# RTL8201CL_Demo.net
KiCad netlist of a schematic drawn in Altium Designer
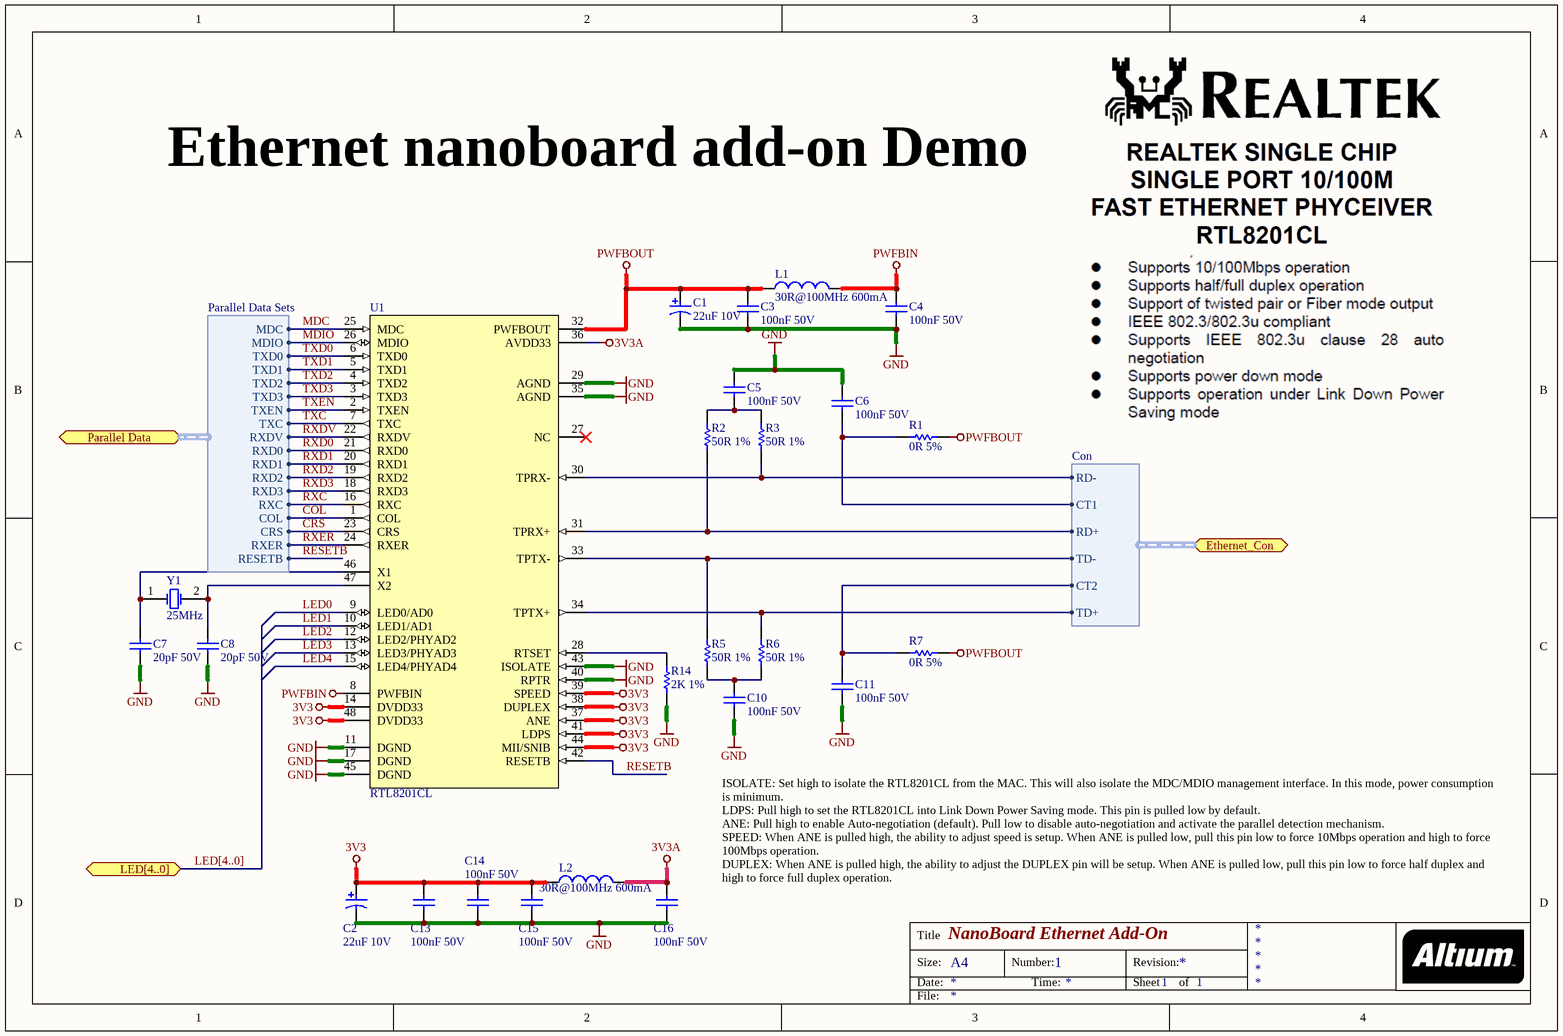
[diagram p0: RTL8201CL_Demo.SchDoc]

(export (version "E")
  (design (tool "Eeschema 10.0.6"))
  (components
    (comp (ref "C1")
      (value "22uF 10V")
      (footprint "PHY_Demo:CAPC3528")
      (description "Polar Capacitor")
      (libsource (lib "Altium Design Library") (part "CAP-P"))
    )
    (comp (ref "C2")
      (value "22uF 10V")
      (footprint "PHY_Demo:CAPC3528")
      (description "Polar Capacitor")
      (libsource (lib "Altium Design Library") (part "CAP-P"))
    )
    (comp (ref "C3")
      (value "100nF 50V")
      (footprint "PHY_Demo:CAPC2012")
      (description "Capacitor")
      (libsource (lib "Altium Design Library") (part "CAP-NP"))
    )
    (comp (ref "C4")
      (value "100nF 50V")
      (footprint "PHY_Demo:CAPC2012")
      (description "Capacitor")
      (libsource (lib "Altium Design Library") (part "CAP-NP"))
    )
    (comp (ref "C5")
      (value "100nF 50V")
      (footprint "PHY_Demo:CAPC2012")
      (description "Capacitor")
      (libsource (lib "Altium Design Library") (part "CAP-NP"))
    )
    (comp (ref "C6")
      (value "100nF 50V")
      (footprint "PHY_Demo:CAPC2012")
      (description "Capacitor")
      (libsource (lib "Altium Design Library") (part "CAP-NP"))
    )
    (comp (ref "C7")
      (value "20pF 50V")
      (footprint "PHY_Demo:CAPC2012")
      (description "Capacitor")
      (libsource (lib "Altium Design Library") (part "CAP-NP"))
    )
    (comp (ref "C8")
      (value "20pF 50V")
      (footprint "PHY_Demo:CAPC2012")
      (description "Capacitor")
      (libsource (lib "Altium Design Library") (part "CAP-NP"))
    )
    (comp (ref "C10")
      (value "100nF 50V")
      (footprint "PHY_Demo:CAPC2012")
      (description "Capacitor")
      (libsource (lib "Altium Design Library") (part "CAP-NP"))
    )
    (comp (ref "C11")
      (value "100nF 50V")
      (footprint "PHY_Demo:CAPC2012")
      (description "Capacitor")
      (libsource (lib "Altium Design Library") (part "CAP-NP"))
    )
    (comp (ref "C13")
      (value "100nF 50V")
      (footprint "PHY_Demo:CAPC2012")
      (description "Capacitor")
      (libsource (lib "Altium Design Library") (part "CAP-NP"))
    )
    (comp (ref "C14")
      (value "100nF 50V")
      (footprint "PHY_Demo:CAPC2012")
      (description "Capacitor")
      (libsource (lib "Altium Design Library") (part "CAP-NP"))
    )
    (comp (ref "C15")
      (value "100nF 50V")
      (footprint "PHY_Demo:CAPC2012")
      (description "Capacitor")
      (libsource (lib "Altium Design Library") (part "CAP-NP"))
    )
    (comp (ref "C16")
      (value "100nF 50V")
      (footprint "PHY_Demo:CAPC2012")
      (description "Capacitor")
      (libsource (lib "Altium Design Library") (part "CAP-NP"))
    )
    (comp (ref "L1")
      (value "30R@100MHz 600mA")
      (footprint "PHY_Demo:INDC2012")
      (description "Ferrite Bead")
      (libsource (lib "Altium Design Library") (part "IND-FER"))
    )
    (comp (ref "L2")
      (value "30R@100MHz 600mA")
      (footprint "PHY_Demo:INDC2012")
      (description "Ferrite Bead")
      (libsource (lib "Altium Design Library") (part "IND-FER"))
    )
    (comp (ref "R1")
      (value "0R 5%")
      (footprint "PHY_Demo:RESC2012")
      (description "Resistor")
      (libsource (lib "Altium Design Library") (part "RES"))
    )
    (comp (ref "R2")
      (value "50R 1%")
      (footprint "PHY_Demo:RESC2012")
      (description "Resistor")
      (libsource (lib "Altium Design Library") (part "RES"))
    )
    (comp (ref "R3")
      (value "50R 1%")
      (footprint "PHY_Demo:RESC2012")
      (description "Resistor")
      (libsource (lib "Altium Design Library") (part "RES"))
    )
    (comp (ref "R5")
      (value "50R 1%")
      (footprint "PHY_Demo:RESC2012")
      (description "Resistor")
      (libsource (lib "Altium Design Library") (part "RES"))
    )
    (comp (ref "R6")
      (value "50R 1%")
      (footprint "PHY_Demo:RESC2012")
      (description "Resistor")
      (libsource (lib "Altium Design Library") (part "RES"))
    )
    (comp (ref "R7")
      (value "0R 5%")
      (footprint "PHY_Demo:RESC2012")
      (description "Resistor")
      (libsource (lib "Altium Design Library") (part "RES"))
    )
    (comp (ref "R14")
      (value "2K 1%")
      (footprint "PHY_Demo:RESC2012")
      (description "Resistor")
      (libsource (lib "Altium Design Library") (part "RES"))
    )
    (comp (ref "U1")
      (value "RTL8201CL")
      (footprint "PHY_Demo:TSQFP50P900X900-48")
      (description "Realtek Ethernet PHY tranceiver")
      (libsource (lib "Altium Design Library") (part "RTL8201CL"))
    )
    (comp (ref "Y1")
      (value "25MHz")
      (footprint "PHY_Demo:XTAL_HC49SMD 20Mhz  +/-30ppm 20pf")
      (description "Surface Mount Crystal")
      (libsource (lib "Altium Design Library") (part "CRYS"))
    )
  )
  (nets
    (net (code "5") (name "/COL") (class "Default")
      (node (ref "U1") (pin "1") (pinfunction "COL_1") (pintype "output"))
    )
    (net (code "6") (name "/CRS") (class "Default")
      (node (ref "U1") (pin "23") (pinfunction "CRS_23") (pintype "output"))
    )
    (net (code "7") (name "/LED0") (class "Default")
      (node (ref "U1") (pin "9") (pinfunction "LED0/AD0_9") (pintype "bidirectional"))
    )
    (net (code "8") (name "/LED1") (class "Default")
      (node (ref "U1") (pin "10") (pinfunction "LED1/AD1_10") (pintype "bidirectional"))
    )
    (net (code "9") (name "/LED2") (class "Default")
      (node (ref "U1") (pin "12") (pinfunction "LED2/PHYAD2_12") (pintype "bidirectional"))
    )
    (net (code "10") (name "/LED3") (class "Default")
      (node (ref "U1") (pin "13") (pinfunction "LED3/PHYAD3_13") (pintype "bidirectional"))
    )
    (net (code "11") (name "/LED4") (class "Default")
      (node (ref "U1") (pin "15") (pinfunction "LED4/PHYAD4_15") (pintype "bidirectional"))
    )
    (net (code "13") (name "/MDC") (class "Default")
      (node (ref "U1") (pin "25") (pinfunction "MDC_25") (pintype "input"))
    )
    (net (code "14") (name "/MDIO") (class "Default")
      (node (ref "U1") (pin "26") (pinfunction "MDIO_26") (pintype "bidirectional"))
    )
    (net (code "15") (name "/RESETB") (class "Default")
      (node (ref "U1") (pin "42") (pinfunction "RESETB_42") (pintype "input"))
    )
    (net (code "16") (name "/RXC") (class "Default")
      (node (ref "U1") (pin "16") (pinfunction "RXC_16") (pintype "output"))
    )
    (net (code "17") (name "/RXD0") (class "Default")
      (node (ref "U1") (pin "21") (pinfunction "RXD0_21") (pintype "output"))
    )
    (net (code "18") (name "/RXD1") (class "Default")
      (node (ref "U1") (pin "20") (pinfunction "RXD1_20") (pintype "output"))
    )
    (net (code "19") (name "/RXD2") (class "Default")
      (node (ref "U1") (pin "19") (pinfunction "RXD2_19") (pintype "output"))
    )
    (net (code "20") (name "/RXD3") (class "Default")
      (node (ref "U1") (pin "18") (pinfunction "RXD3_18") (pintype "output"))
    )
    (net (code "21") (name "/RXDV") (class "Default")
      (node (ref "U1") (pin "22") (pinfunction "RXDV_22") (pintype "output"))
    )
    (net (code "22") (name "/RXER") (class "Default")
      (node (ref "U1") (pin "24") (pinfunction "RXER_24") (pintype "output"))
    )
    (net (code "23") (name "/TXC") (class "Default")
      (node (ref "U1") (pin "7") (pinfunction "TXC_7") (pintype "output"))
    )
    (net (code "24") (name "/TXD0") (class "Default")
      (node (ref "U1") (pin "6") (pinfunction "TXD0_6") (pintype "input"))
    )
    (net (code "25") (name "/TXD1") (class "Default")
      (node (ref "U1") (pin "5") (pinfunction "TXD1_5") (pintype "input"))
    )
    (net (code "26") (name "/TXD2") (class "Default")
      (node (ref "U1") (pin "4") (pinfunction "TXD2_4") (pintype "input"))
    )
    (net (code "27") (name "/TXD3") (class "Default")
      (node (ref "U1") (pin "3") (pinfunction "TXD3_3") (pintype "input"))
    )
    (net (code "28") (name "/TXEN") (class "Default")
      (node (ref "U1") (pin "2") (pinfunction "TXEN_2") (pintype "input"))
    )
    (net (code "31") (name "3V3") (class "Default")
      (node (ref "C13") (pin "2") (pinfunction "2_2") (pintype "passive"))
      (node (ref "C14") (pin "2") (pinfunction "2_2") (pintype "passive"))
      (node (ref "C15") (pin "2") (pinfunction "2_2") (pintype "passive"))
      (node (ref "C2") (pin "1") (pinfunction "1_1") (pintype "passive"))
      (node (ref "L2") (pin "1") (pinfunction "1_1") (pintype "passive"))
      (node (ref "U1") (pin "14") (pinfunction "DVDD33_14") (pintype "power_in"))
      (node (ref "U1") (pin "37") (pinfunction "ANE_37") (pintype "input"))
      (node (ref "U1") (pin "38") (pinfunction "DUPLEX_38") (pintype "input"))
      (node (ref "U1") (pin "39") (pinfunction "SPEED_39") (pintype "input"))
      (node (ref "U1") (pin "41") (pinfunction "LDPS_41") (pintype "input"))
      (node (ref "U1") (pin "44") (pinfunction "MII/SNIB_44") (pintype "input"))
      (node (ref "U1") (pin "48") (pinfunction "DVDD33_48") (pintype "power_in"))
    )
    (net (code "32") (name "3V3A") (class "Default")
      (node (ref "C16") (pin "2") (pinfunction "2_2") (pintype "passive"))
      (node (ref "L2") (pin "2") (pinfunction "2_2") (pintype "passive"))
      (node (ref "U1") (pin "36") (pinfunction "AVDD33_36") (pintype "power_in"))
    )
    (net (code "33") (name "GND") (class "Default")
      (node (ref "C1") (pin "2") (pinfunction "2_2") (pintype "passive"))
      (node (ref "C10") (pin "1") (pinfunction "1_1") (pintype "passive"))
      (node (ref "C11") (pin "1") (pinfunction "1_1") (pintype "passive"))
      (node (ref "C13") (pin "1") (pinfunction "1_1") (pintype "passive"))
      (node (ref "C14") (pin "1") (pinfunction "1_1") (pintype "passive"))
      (node (ref "C15") (pin "1") (pinfunction "1_1") (pintype "passive"))
      (node (ref "C16") (pin "1") (pinfunction "1_1") (pintype "passive"))
      (node (ref "C2") (pin "2") (pinfunction "2_2") (pintype "passive"))
      (node (ref "C3") (pin "1") (pinfunction "1_1") (pintype "passive"))
      (node (ref "C4") (pin "1") (pinfunction "1_1") (pintype "passive"))
      (node (ref "C5") (pin "2") (pinfunction "2_2") (pintype "passive"))
      (node (ref "C6") (pin "1") (pinfunction "1_1") (pintype "passive"))
      (node (ref "C7") (pin "1") (pinfunction "1_1") (pintype "passive"))
      (node (ref "C8") (pin "1") (pinfunction "1_1") (pintype "passive"))
      (node (ref "R14") (pin "1") (pinfunction "1_1") (pintype "passive"))
      (node (ref "U1") (pin "11") (pinfunction "DGND_11") (pintype "power_in"))
      (node (ref "U1") (pin "17") (pinfunction "DGND_17") (pintype "power_in"))
      (node (ref "U1") (pin "29") (pinfunction "AGND_29") (pintype "power_in"))
      (node (ref "U1") (pin "35") (pinfunction "AGND_35") (pintype "power_in"))
      (node (ref "U1") (pin "40") (pinfunction "RPTR_40") (pintype "input"))
      (node (ref "U1") (pin "43") (pinfunction "ISOLATE_43") (pintype "input"))
      (node (ref "U1") (pin "45") (pinfunction "DGND_45") (pintype "power_in"))
    )
    (net (code "34") (name "Net-(C5-Pad1)") (class "Default")
      (node (ref "C5") (pin "1") (pinfunction "1_1") (pintype "passive"))
      (node (ref "R2") (pin "2") (pinfunction "2_2") (pintype "passive"))
      (node (ref "R3") (pin "2") (pinfunction "2_2") (pintype "passive"))
    )
    (net (code "35") (name "Net-(C6-Pad2)") (class "Default")
      (node (ref "C6") (pin "2") (pinfunction "2_2") (pintype "passive"))
      (node (ref "R1") (pin "1") (pinfunction "1_1") (pintype "passive"))
    )
    (net (code "36") (name "Net-(C10-Pad2)") (class "Default")
      (node (ref "C10") (pin "2") (pinfunction "2_2") (pintype "passive"))
      (node (ref "R5") (pin "1") (pinfunction "1_1") (pintype "passive"))
      (node (ref "R6") (pin "1") (pinfunction "1_1") (pintype "passive"))
    )
    (net (code "37") (name "Net-(C11-Pad2)") (class "Default")
      (node (ref "C11") (pin "2") (pinfunction "2_2") (pintype "passive"))
      (node (ref "R7") (pin "1") (pinfunction "1_1") (pintype "passive"))
    )
    (net (code "38") (name "Net-(U1-RTSET)") (class "Default")
      (node (ref "R14") (pin "2") (pinfunction "2_2") (pintype "passive"))
      (node (ref "U1") (pin "28") (pinfunction "RTSET_28") (pintype "input"))
    )
    (net (code "39") (name "Net-(U1-TPRX+)") (class "Default")
      (node (ref "R2") (pin "1") (pinfunction "1_1") (pintype "passive"))
      (node (ref "U1") (pin "31") (pinfunction "TPRX+_31") (pintype "input"))
    )
    (net (code "40") (name "Net-(U1-TPRX-)") (class "Default")
      (node (ref "R3") (pin "1") (pinfunction "1_1") (pintype "passive"))
      (node (ref "U1") (pin "30") (pinfunction "TPRX-_30") (pintype "input"))
    )
    (net (code "41") (name "Net-(U1-TPTX+)") (class "Default")
      (node (ref "R6") (pin "2") (pinfunction "2_2") (pintype "passive"))
      (node (ref "U1") (pin "34") (pinfunction "TPTX+_34") (pintype "output"))
    )
    (net (code "42") (name "Net-(U1-TPTX-)") (class "Default")
      (node (ref "R5") (pin "2") (pinfunction "2_2") (pintype "passive"))
      (node (ref "U1") (pin "33") (pinfunction "TPTX-_33") (pintype "output"))
    )
    (net (code "43") (name "Net-(U1-X1)") (class "Default")
      (node (ref "C7") (pin "2") (pinfunction "2_2") (pintype "passive"))
      (node (ref "U1") (pin "46") (pinfunction "X1_46") (pintype "passive"))
      (node (ref "Y1") (pin "1") (pinfunction "OSC1_1") (pintype "passive"))
    )
    (net (code "44") (name "Net-(U1-X2)") (class "Default")
      (node (ref "C8") (pin "2") (pinfunction "2_2") (pintype "passive"))
      (node (ref "U1") (pin "47") (pinfunction "X2_47") (pintype "passive"))
      (node (ref "Y1") (pin "2") (pinfunction "OSC2_2") (pintype "passive"))
    )
    (net (code "45") (name "PWFBIN") (class "Default")
      (node (ref "C4") (pin "2") (pinfunction "2_2") (pintype "passive"))
      (node (ref "L1") (pin "2") (pinfunction "2_2") (pintype "passive"))
      (node (ref "U1") (pin "8") (pinfunction "PWFBIN_8") (pintype "power_in"))
    )
    (net (code "46") (name "PWFBOUT") (class "Default")
      (node (ref "C1") (pin "1") (pinfunction "1_1") (pintype "passive"))
      (node (ref "C3") (pin "2") (pinfunction "2_2") (pintype "passive"))
      (node (ref "L1") (pin "1") (pinfunction "1_1") (pintype "passive"))
      (node (ref "R1") (pin "2") (pinfunction "2_2") (pintype "passive"))
      (node (ref "R7") (pin "2") (pinfunction "2_2") (pintype "passive"))
      (node (ref "U1") (pin "32") (pinfunction "PWFBOUT_32") (pintype "power_in"))
    )
    (net (code "47") (name "unconnected-(U1-NC-Pad27)") (class "Default")
      (node (ref "U1") (pin "27") (pinfunction "NC_27") (pintype "passive+no_connect"))
    )
  )
)
